# MultiChannelLdc3.net
KiCad netlist of a schematic drawn in Altium Designer
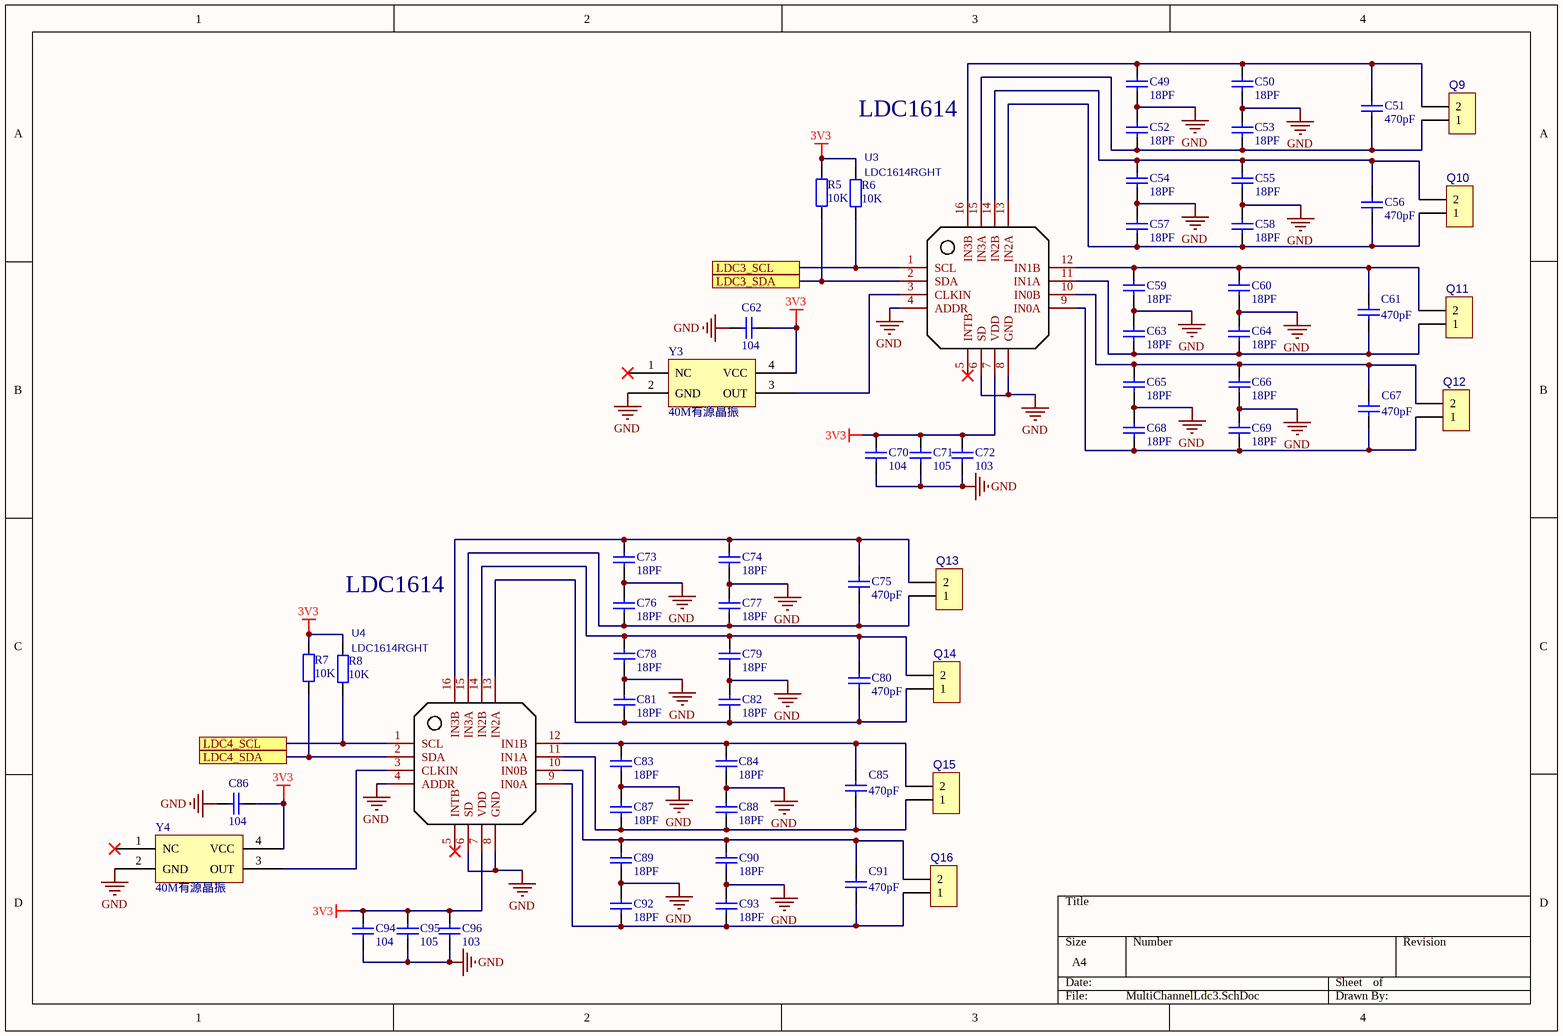
[diagram p0: MultiChannelLdc3.SchDoc]

(export (version "E")
  (design (tool "Eeschema 10.0.6"))
  (components
    (comp (ref "C49")
      (value "18PF")
      (footprint "C0603_L")
      (description "Capacitor")
      (fields (field (name "PUBLISHER") "Altium Limited"))
      (libsource (lib "STM32F103C8T6") (part "Cap"))
    )
    (comp (ref "C50")
      (value "18PF")
      (footprint "C0603_L")
      (description "Capacitor")
      (fields (field (name "PUBLISHER") "Altium Limited"))
      (libsource (lib "STM32F103C8T6") (part "Cap"))
    )
    (comp (ref "C51")
      (value "470pF")
      (footprint "C0603_L")
      (description "Capacitor")
      (fields (field (name "PUBLISHER") "Altium Limited"))
      (libsource (lib "STM32F103C8T6") (part "Cap"))
    )
    (comp (ref "C52")
      (value "18PF")
      (footprint "C0603_L")
      (description "Capacitor")
      (fields (field (name "PUBLISHER") "Altium Limited"))
      (libsource (lib "STM32F103C8T6") (part "Cap"))
    )
    (comp (ref "C53")
      (value "18PF")
      (footprint "C0603_L")
      (description "Capacitor")
      (fields (field (name "PUBLISHER") "Altium Limited"))
      (libsource (lib "STM32F103C8T6") (part "Cap"))
    )
    (comp (ref "C54")
      (value "18PF")
      (footprint "C0603_L")
      (description "Capacitor")
      (fields (field (name "PUBLISHER") "Altium Limited"))
      (libsource (lib "STM32F103C8T6") (part "Cap"))
    )
    (comp (ref "C55")
      (value "18PF")
      (footprint "C0603_L")
      (description "Capacitor")
      (fields (field (name "PUBLISHER") "Altium Limited"))
      (libsource (lib "STM32F103C8T6") (part "Cap"))
    )
    (comp (ref "C56")
      (value "470pF")
      (footprint "C0603_L")
      (description "Capacitor")
      (fields (field (name "PUBLISHER") "Altium Limited"))
      (libsource (lib "STM32F103C8T6") (part "Cap"))
    )
    (comp (ref "C57")
      (value "18PF")
      (footprint "C0603_L")
      (description "Capacitor")
      (fields (field (name "PUBLISHER") "Altium Limited"))
      (libsource (lib "STM32F103C8T6") (part "Cap"))
    )
    (comp (ref "C58")
      (value "18PF")
      (footprint "C0603_L")
      (description "Capacitor")
      (fields (field (name "PUBLISHER") "Altium Limited"))
      (libsource (lib "STM32F103C8T6") (part "Cap"))
    )
    (comp (ref "C59")
      (value "18PF")
      (footprint "C0603_L")
      (description "Capacitor")
      (fields (field (name "PUBLISHER") "Altium Limited"))
      (libsource (lib "STM32F103C8T6") (part "Cap"))
    )
    (comp (ref "C60")
      (value "18PF")
      (footprint "C0603_L")
      (description "Capacitor")
      (fields (field (name "PUBLISHER") "Altium Limited"))
      (libsource (lib "STM32F103C8T6") (part "Cap"))
    )
    (comp (ref "C61")
      (value "470pF")
      (footprint "C0603_L")
      (description "Capacitor")
      (fields (field (name "PUBLISHER") "Altium Limited"))
      (libsource (lib "STM32F103C8T6") (part "Cap"))
    )
    (comp (ref "C62")
      (value "104")
      (footprint "C0603_L")
      (description "贴片电容/MLCC电容")
      (libsource (lib "Ldc1614_Pro") (part "C"))
    )
    (comp (ref "C63")
      (value "18PF")
      (footprint "C0603_L")
      (description "Capacitor")
      (fields (field (name "PUBLISHER") "Altium Limited"))
      (libsource (lib "STM32F103C8T6") (part "Cap"))
    )
    (comp (ref "C64")
      (value "18PF")
      (footprint "C0603_L")
      (description "Capacitor")
      (fields (field (name "PUBLISHER") "Altium Limited"))
      (libsource (lib "STM32F103C8T6") (part "Cap"))
    )
    (comp (ref "C65")
      (value "18PF")
      (footprint "C0603_L")
      (description "Capacitor")
      (fields (field (name "PUBLISHER") "Altium Limited"))
      (libsource (lib "STM32F103C8T6") (part "Cap"))
    )
    (comp (ref "C66")
      (value "18PF")
      (footprint "C0603_L")
      (description "Capacitor")
      (fields (field (name "PUBLISHER") "Altium Limited"))
      (libsource (lib "STM32F103C8T6") (part "Cap"))
    )
    (comp (ref "C67")
      (value "470pF")
      (footprint "C0603_L")
      (description "Capacitor")
      (fields (field (name "PUBLISHER") "Altium Limited"))
      (libsource (lib "STM32F103C8T6") (part "Cap"))
    )
    (comp (ref "C68")
      (value "18PF")
      (footprint "C0603_L")
      (description "Capacitor")
      (fields (field (name "PUBLISHER") "Altium Limited"))
      (libsource (lib "STM32F103C8T6") (part "Cap"))
    )
    (comp (ref "C69")
      (value "18PF")
      (footprint "C0603_L")
      (description "Capacitor")
      (fields (field (name "PUBLISHER") "Altium Limited"))
      (libsource (lib "STM32F103C8T6") (part "Cap"))
    )
    (comp (ref "C70")
      (value "104")
      (footprint "C0603_L")
      (description "Capacitor")
      (fields (field (name "PUBLISHER") "Altium Limited"))
      (libsource (lib "STM32F103C8T6") (part "Cap"))
    )
    (comp (ref "C71")
      (value "105")
      (footprint "C0603_L")
      (description "Capacitor")
      (fields (field (name "PUBLISHER") "Altium Limited"))
      (libsource (lib "STM32F103C8T6") (part "Cap"))
    )
    (comp (ref "C72")
      (value "103")
      (footprint "C0603_L")
      (description "Capacitor")
      (fields (field (name "PUBLISHER") "Altium Limited"))
      (libsource (lib "STM32F103C8T6") (part "Cap"))
    )
    (comp (ref "C73")
      (value "18PF")
      (footprint "C0603_L")
      (description "Capacitor")
      (fields (field (name "PUBLISHER") "Altium Limited"))
      (libsource (lib "STM32F103C8T6") (part "Cap"))
    )
    (comp (ref "C74")
      (value "18PF")
      (footprint "C0603_L")
      (description "Capacitor")
      (fields (field (name "PUBLISHER") "Altium Limited"))
      (libsource (lib "STM32F103C8T6") (part "Cap"))
    )
    (comp (ref "C75")
      (value "470pF")
      (footprint "C0603_L")
      (description "Capacitor")
      (fields (field (name "PUBLISHER") "Altium Limited"))
      (libsource (lib "STM32F103C8T6") (part "Cap"))
    )
    (comp (ref "C76")
      (value "18PF")
      (footprint "C0603_L")
      (description "Capacitor")
      (fields (field (name "PUBLISHER") "Altium Limited"))
      (libsource (lib "STM32F103C8T6") (part "Cap"))
    )
    (comp (ref "C77")
      (value "18PF")
      (footprint "C0603_L")
      (description "Capacitor")
      (fields (field (name "PUBLISHER") "Altium Limited"))
      (libsource (lib "STM32F103C8T6") (part "Cap"))
    )
    (comp (ref "C78")
      (value "18PF")
      (footprint "C0603_L")
      (description "Capacitor")
      (fields (field (name "PUBLISHER") "Altium Limited"))
      (libsource (lib "STM32F103C8T6") (part "Cap"))
    )
    (comp (ref "C79")
      (value "18PF")
      (footprint "C0603_L")
      (description "Capacitor")
      (fields (field (name "PUBLISHER") "Altium Limited"))
      (libsource (lib "STM32F103C8T6") (part "Cap"))
    )
    (comp (ref "C80")
      (value "470pF")
      (footprint "C0603_L")
      (description "Capacitor")
      (fields (field (name "PUBLISHER") "Altium Limited"))
      (libsource (lib "STM32F103C8T6") (part "Cap"))
    )
    (comp (ref "C81")
      (value "18PF")
      (footprint "C0603_L")
      (description "Capacitor")
      (fields (field (name "PUBLISHER") "Altium Limited"))
      (libsource (lib "STM32F103C8T6") (part "Cap"))
    )
    (comp (ref "C82")
      (value "18PF")
      (footprint "C0603_L")
      (description "Capacitor")
      (fields (field (name "PUBLISHER") "Altium Limited"))
      (libsource (lib "STM32F103C8T6") (part "Cap"))
    )
    (comp (ref "C83")
      (value "18PF")
      (footprint "C0603_L")
      (description "Capacitor")
      (fields (field (name "PUBLISHER") "Altium Limited"))
      (libsource (lib "STM32F103C8T6") (part "Cap"))
    )
    (comp (ref "C84")
      (value "18PF")
      (footprint "C0603_L")
      (description "Capacitor")
      (fields (field (name "PUBLISHER") "Altium Limited"))
      (libsource (lib "STM32F103C8T6") (part "Cap"))
    )
    (comp (ref "C85")
      (value "470pF")
      (footprint "C0603_L")
      (description "Capacitor")
      (fields (field (name "PUBLISHER") "Altium Limited"))
      (libsource (lib "STM32F103C8T6") (part "Cap"))
    )
    (comp (ref "C86")
      (value "104")
      (footprint "C0603_L")
      (description "贴片电容/MLCC电容")
      (libsource (lib "Ldc1614_Pro") (part "C"))
    )
    (comp (ref "C87")
      (value "18PF")
      (footprint "C0603_L")
      (description "Capacitor")
      (fields (field (name "PUBLISHER") "Altium Limited"))
      (libsource (lib "STM32F103C8T6") (part "Cap"))
    )
    (comp (ref "C88")
      (value "18PF")
      (footprint "C0603_L")
      (description "Capacitor")
      (fields (field (name "PUBLISHER") "Altium Limited"))
      (libsource (lib "STM32F103C8T6") (part "Cap"))
    )
    (comp (ref "C89")
      (value "18PF")
      (footprint "C0603_L")
      (description "Capacitor")
      (fields (field (name "PUBLISHER") "Altium Limited"))
      (libsource (lib "STM32F103C8T6") (part "Cap"))
    )
    (comp (ref "C90")
      (value "18PF")
      (footprint "C0603_L")
      (description "Capacitor")
      (fields (field (name "PUBLISHER") "Altium Limited"))
      (libsource (lib "STM32F103C8T6") (part "Cap"))
    )
    (comp (ref "C91")
      (value "470pF")
      (footprint "C0603_L")
      (description "Capacitor")
      (fields (field (name "PUBLISHER") "Altium Limited"))
      (libsource (lib "STM32F103C8T6") (part "Cap"))
    )
    (comp (ref "C92")
      (value "18PF")
      (footprint "C0603_L")
      (description "Capacitor")
      (fields (field (name "PUBLISHER") "Altium Limited"))
      (libsource (lib "STM32F103C8T6") (part "Cap"))
    )
    (comp (ref "C93")
      (value "18PF")
      (footprint "C0603_L")
      (description "Capacitor")
      (fields (field (name "PUBLISHER") "Altium Limited"))
      (libsource (lib "STM32F103C8T6") (part "Cap"))
    )
    (comp (ref "C94")
      (value "104")
      (footprint "C0603_L")
      (description "Capacitor")
      (fields (field (name "PUBLISHER") "Altium Limited"))
      (libsource (lib "STM32F103C8T6") (part "Cap"))
    )
    (comp (ref "C95")
      (value "105")
      (footprint "C0603_L")
      (description "Capacitor")
      (fields (field (name "PUBLISHER") "Altium Limited"))
      (libsource (lib "STM32F103C8T6") (part "Cap"))
    )
    (comp (ref "C96")
      (value "103")
      (footprint "C0603_L")
      (description "Capacitor")
      (fields (field (name "PUBLISHER") "Altium Limited"))
      (libsource (lib "STM32F103C8T6") (part "Cap"))
    )
    (comp (ref "Q9")
      (value "~")
      (footprint "座子")
      (description "Connector")
      (libsource (lib "*") (part "CON2"))
    )
    (comp (ref "Q10")
      (value "~")
      (footprint "座子")
      (description "Connector")
      (libsource (lib "*") (part "CON2"))
    )
    (comp (ref "Q11")
      (value "~")
      (footprint "座子")
      (description "Connector")
      (libsource (lib "*") (part "CON2"))
    )
    (comp (ref "Q12")
      (value "~")
      (footprint "座子")
      (description "Connector")
      (libsource (lib "*") (part "CON2"))
    )
    (comp (ref "Q13")
      (value "~")
      (footprint "座子")
      (description "Connector")
      (libsource (lib "*") (part "CON2"))
    )
    (comp (ref "Q14")
      (value "~")
      (footprint "座子")
      (description "Connector")
      (libsource (lib "*") (part "CON2"))
    )
    (comp (ref "Q15")
      (value "~")
      (footprint "座子")
      (description "Connector")
      (libsource (lib "*") (part "CON2"))
    )
    (comp (ref "Q16")
      (value "~")
      (footprint "座子")
      (description "Connector")
      (libsource (lib "*") (part "CON2"))
    )
    (comp (ref "R5")
      (value "10K")
      (footprint "R0603_L")
      (description "Resistor")
      (fields (field (name "Comment") "Res2") (field (name "PUBLISHER") "Altium Limited"))
      (libsource (lib "LDC") (part "Res2"))
    )
    (comp (ref "R6")
      (value "10K")
      (footprint "R0603_L")
      (description "Resistor")
      (fields (field (name "Comment") "Res2") (field (name "PUBLISHER") "Altium Limited"))
      (libsource (lib "Miscellaneous Devices") (part "Res2"))
    )
    (comp (ref "R7")
      (value "10K")
      (footprint "R0603_L")
      (description "Resistor")
      (fields (field (name "Comment") "Res2") (field (name "PUBLISHER") "Altium Limited"))
      (libsource (lib "LDC") (part "Res2"))
    )
    (comp (ref "R8")
      (value "10K")
      (footprint "R0603_L")
      (description "Resistor")
      (fields (field (name "Comment") "Res2") (field (name "PUBLISHER") "Altium Limited"))
      (libsource (lib "Miscellaneous Devices") (part "Res2"))
    )
    (comp (ref "U3")
      (value "LDC1614RGHT")
      (footprint "W-QFN-16")
      (fields
        (field (name "BOM_MANUFACTURER PART") "LDC1314RGHT")
        (field (name "BOM_SUPPLIER PART") "C80399")
      )
      (libsource (lib "LDC1614") (part "LDC1614RGHT"))
    )
    (comp (ref "U4")
      (value "LDC1614RGHT")
      (footprint "W-QFN-16")
      (fields
        (field (name "BOM_MANUFACTURER PART") "LDC1314RGHT")
        (field (name "BOM_SUPPLIER PART") "C80399")
      )
      (libsource (lib "LDC1614") (part "LDC1614RGHT"))
    )
    (comp (ref "Y3") (value "40M有源晶振") (footprint "SMD3225") (libsource (lib "其他常用元件类") (part "有源晶振")))
    (comp (ref "Y4") (value "40M有源晶振") (footprint "SMD3225") (libsource (lib "其他常用元件类") (part "有源晶振")))
  )
  (nets
    (net (code "1") (name "/LDC3_SCL") (class "Default")
      (node (ref "U3") (pin "1") (pinfunction "SCL_1") (pintype "passive"))
    )
    (net (code "2") (name "/LDC3_SDA") (class "Default")
      (node (ref "R5") (pin "1") (pinfunction "1_1") (pintype "passive"))
      (node (ref "U3") (pin "2") (pinfunction "SDA_2") (pintype "passive"))
    )
    (net (code "3") (name "/LDC4_SCL") (class "Default")
      (node (ref "U4") (pin "1") (pinfunction "SCL_1") (pintype "passive"))
    )
    (net (code "4") (name "/LDC4_SDA") (class "Default")
      (node (ref "R7") (pin "1") (pinfunction "1_1") (pintype "passive"))
      (node (ref "U4") (pin "2") (pinfunction "SDA_2") (pintype "passive"))
    )
    (net (code "5") (name "3V3") (class "Default")
      (node (ref "C62") (pin "1") (pinfunction "1_1") (pintype "passive"))
      (node (ref "C70") (pin "1") (pinfunction "1_1") (pintype "passive"))
      (node (ref "C71") (pin "1") (pinfunction "1_1") (pintype "passive"))
      (node (ref "C72") (pin "1") (pinfunction "1_1") (pintype "passive"))
      (node (ref "C86") (pin "1") (pinfunction "1_1") (pintype "passive"))
      (node (ref "C94") (pin "1") (pinfunction "1_1") (pintype "passive"))
      (node (ref "C95") (pin "1") (pinfunction "1_1") (pintype "passive"))
      (node (ref "C96") (pin "1") (pinfunction "1_1") (pintype "passive"))
      (node (ref "R5") (pin "2") (pinfunction "2_2") (pintype "passive"))
      (node (ref "R6") (pin "1") (pinfunction "1_1") (pintype "passive"))
      (node (ref "R7") (pin "2") (pinfunction "2_2") (pintype "passive"))
      (node (ref "R8") (pin "1") (pinfunction "1_1") (pintype "passive"))
      (node (ref "U3") (pin "7") (pinfunction "VDD_7") (pintype "passive"))
      (node (ref "U4") (pin "7") (pinfunction "VDD_7") (pintype "passive"))
      (node (ref "Y3") (pin "4") (pinfunction "VCC_4") (pintype "passive"))
      (node (ref "Y4") (pin "4") (pinfunction "VCC_4") (pintype "passive"))
    )
    (net (code "6") (name "GND") (class "Default")
      (node (ref "C49") (pin "2") (pinfunction "2_2") (pintype "passive"))
      (node (ref "C50") (pin "2") (pinfunction "2_2") (pintype "passive"))
      (node (ref "C52") (pin "1") (pinfunction "1_1") (pintype "passive"))
      (node (ref "C53") (pin "1") (pinfunction "1_1") (pintype "passive"))
      (node (ref "C54") (pin "2") (pinfunction "2_2") (pintype "passive"))
      (node (ref "C55") (pin "2") (pinfunction "2_2") (pintype "passive"))
      (node (ref "C57") (pin "1") (pinfunction "1_1") (pintype "passive"))
      (node (ref "C58") (pin "1") (pinfunction "1_1") (pintype "passive"))
      (node (ref "C59") (pin "2") (pinfunction "2_2") (pintype "passive"))
      (node (ref "C60") (pin "2") (pinfunction "2_2") (pintype "passive"))
      (node (ref "C62") (pin "2") (pinfunction "2_2") (pintype "passive"))
      (node (ref "C63") (pin "1") (pinfunction "1_1") (pintype "passive"))
      (node (ref "C64") (pin "1") (pinfunction "1_1") (pintype "passive"))
      (node (ref "C65") (pin "2") (pinfunction "2_2") (pintype "passive"))
      (node (ref "C66") (pin "2") (pinfunction "2_2") (pintype "passive"))
      (node (ref "C68") (pin "1") (pinfunction "1_1") (pintype "passive"))
      (node (ref "C69") (pin "1") (pinfunction "1_1") (pintype "passive"))
      (node (ref "C70") (pin "2") (pinfunction "2_2") (pintype "passive"))
      (node (ref "C71") (pin "2") (pinfunction "2_2") (pintype "passive"))
      (node (ref "C72") (pin "2") (pinfunction "2_2") (pintype "passive"))
      (node (ref "C73") (pin "2") (pinfunction "2_2") (pintype "passive"))
      (node (ref "C74") (pin "2") (pinfunction "2_2") (pintype "passive"))
      (node (ref "C76") (pin "1") (pinfunction "1_1") (pintype "passive"))
      (node (ref "C77") (pin "1") (pinfunction "1_1") (pintype "passive"))
      (node (ref "C78") (pin "2") (pinfunction "2_2") (pintype "passive"))
      (node (ref "C79") (pin "2") (pinfunction "2_2") (pintype "passive"))
      (node (ref "C81") (pin "1") (pinfunction "1_1") (pintype "passive"))
      (node (ref "C82") (pin "1") (pinfunction "1_1") (pintype "passive"))
      (node (ref "C83") (pin "2") (pinfunction "2_2") (pintype "passive"))
      (node (ref "C84") (pin "2") (pinfunction "2_2") (pintype "passive"))
      (node (ref "C86") (pin "2") (pinfunction "2_2") (pintype "passive"))
      (node (ref "C87") (pin "1") (pinfunction "1_1") (pintype "passive"))
      (node (ref "C88") (pin "1") (pinfunction "1_1") (pintype "passive"))
      (node (ref "C89") (pin "2") (pinfunction "2_2") (pintype "passive"))
      (node (ref "C90") (pin "2") (pinfunction "2_2") (pintype "passive"))
      (node (ref "C92") (pin "1") (pinfunction "1_1") (pintype "passive"))
      (node (ref "C93") (pin "1") (pinfunction "1_1") (pintype "passive"))
      (node (ref "C94") (pin "2") (pinfunction "2_2") (pintype "passive"))
      (node (ref "C95") (pin "2") (pinfunction "2_2") (pintype "passive"))
      (node (ref "C96") (pin "2") (pinfunction "2_2") (pintype "passive"))
      (node (ref "U3") (pin "4") (pinfunction "ADDR_4") (pintype "passive"))
      (node (ref "U3") (pin "6") (pinfunction "SD_6") (pintype "passive"))
      (node (ref "U3") (pin "8") (pinfunction "GND_8") (pintype "passive"))
      (node (ref "U4") (pin "4") (pinfunction "ADDR_4") (pintype "passive"))
      (node (ref "U4") (pin "6") (pinfunction "SD_6") (pintype "passive"))
      (node (ref "U4") (pin "8") (pinfunction "GND_8") (pintype "passive"))
      (node (ref "Y3") (pin "2") (pinfunction "GND_2") (pintype "passive"))
      (node (ref "Y4") (pin "2") (pinfunction "GND_2") (pintype "passive"))
    )
    (net (code "7") (name "Net-(U3-CLKIN)") (class "Default")
      (node (ref "U3") (pin "3") (pinfunction "CLKIN_3") (pintype "passive"))
      (node (ref "Y3") (pin "3") (pinfunction "OUT_3") (pintype "passive"))
    )
    (net (code "8") (name "Net-(U3-IN0A)") (class "Default")
      (node (ref "C67") (pin "1") (pinfunction "1_1") (pintype "passive"))
      (node (ref "C68") (pin "2") (pinfunction "2_2") (pintype "passive"))
      (node (ref "C69") (pin "2") (pinfunction "2_2") (pintype "passive"))
      (node (ref "Q12") (pin "1") (pinfunction "1_1") (pintype "passive"))
      (node (ref "U3") (pin "9") (pinfunction "IN0A_9") (pintype "passive"))
    )
    (net (code "9") (name "Net-(U3-IN0B)") (class "Default")
      (node (ref "C65") (pin "1") (pinfunction "1_1") (pintype "passive"))
      (node (ref "C66") (pin "1") (pinfunction "1_1") (pintype "passive"))
      (node (ref "C67") (pin "2") (pinfunction "2_2") (pintype "passive"))
      (node (ref "Q12") (pin "2") (pinfunction "2_2") (pintype "passive"))
      (node (ref "U3") (pin "10") (pinfunction "IN0B_10") (pintype "passive"))
    )
    (net (code "10") (name "Net-(U3-IN1A)") (class "Default")
      (node (ref "C61") (pin "1") (pinfunction "1_1") (pintype "passive"))
      (node (ref "C63") (pin "2") (pinfunction "2_2") (pintype "passive"))
      (node (ref "C64") (pin "2") (pinfunction "2_2") (pintype "passive"))
      (node (ref "Q11") (pin "1") (pinfunction "1_1") (pintype "passive"))
      (node (ref "U3") (pin "11") (pinfunction "IN1A_11") (pintype "passive"))
    )
    (net (code "11") (name "Net-(U3-IN1B)") (class "Default")
      (node (ref "C59") (pin "1") (pinfunction "1_1") (pintype "passive"))
      (node (ref "C60") (pin "1") (pinfunction "1_1") (pintype "passive"))
      (node (ref "C61") (pin "2") (pinfunction "2_2") (pintype "passive"))
      (node (ref "Q11") (pin "2") (pinfunction "2_2") (pintype "passive"))
      (node (ref "U3") (pin "12") (pinfunction "IN1B_12") (pintype "passive"))
    )
    (net (code "12") (name "Net-(U3-IN2A)") (class "Default")
      (node (ref "C56") (pin "1") (pinfunction "1_1") (pintype "passive"))
      (node (ref "C57") (pin "2") (pinfunction "2_2") (pintype "passive"))
      (node (ref "C58") (pin "2") (pinfunction "2_2") (pintype "passive"))
      (node (ref "Q10") (pin "1") (pinfunction "1_1") (pintype "passive"))
      (node (ref "U3") (pin "13") (pinfunction "IN2A_13") (pintype "passive"))
    )
    (net (code "13") (name "Net-(U3-IN2B)") (class "Default")
      (node (ref "C54") (pin "1") (pinfunction "1_1") (pintype "passive"))
      (node (ref "C55") (pin "1") (pinfunction "1_1") (pintype "passive"))
      (node (ref "C56") (pin "2") (pinfunction "2_2") (pintype "passive"))
      (node (ref "Q10") (pin "2") (pinfunction "2_2") (pintype "passive"))
      (node (ref "U3") (pin "14") (pinfunction "IN2B_14") (pintype "passive"))
    )
    (net (code "14") (name "Net-(U3-IN3A)") (class "Default")
      (node (ref "C51") (pin "1") (pinfunction "1_1") (pintype "passive"))
      (node (ref "C52") (pin "2") (pinfunction "2_2") (pintype "passive"))
      (node (ref "C53") (pin "2") (pinfunction "2_2") (pintype "passive"))
      (node (ref "Q9") (pin "1") (pinfunction "1_1") (pintype "passive"))
      (node (ref "U3") (pin "15") (pinfunction "IN3A_15") (pintype "passive"))
    )
    (net (code "15") (name "Net-(U3-IN3B)") (class "Default")
      (node (ref "C49") (pin "1") (pinfunction "1_1") (pintype "passive"))
      (node (ref "C50") (pin "1") (pinfunction "1_1") (pintype "passive"))
      (node (ref "C51") (pin "2") (pinfunction "2_2") (pintype "passive"))
      (node (ref "Q9") (pin "2") (pinfunction "2_2") (pintype "passive"))
      (node (ref "U3") (pin "16") (pinfunction "IN3B_16") (pintype "passive"))
    )
    (net (code "16") (name "Net-(U4-CLKIN)") (class "Default")
      (node (ref "U4") (pin "3") (pinfunction "CLKIN_3") (pintype "passive"))
      (node (ref "Y4") (pin "3") (pinfunction "OUT_3") (pintype "passive"))
    )
    (net (code "17") (name "Net-(U4-IN0A)") (class "Default")
      (node (ref "C91") (pin "1") (pinfunction "1_1") (pintype "passive"))
      (node (ref "C92") (pin "2") (pinfunction "2_2") (pintype "passive"))
      (node (ref "C93") (pin "2") (pinfunction "2_2") (pintype "passive"))
      (node (ref "Q16") (pin "1") (pinfunction "1_1") (pintype "passive"))
      (node (ref "U4") (pin "9") (pinfunction "IN0A_9") (pintype "passive"))
    )
    (net (code "18") (name "Net-(U4-IN0B)") (class "Default")
      (node (ref "C89") (pin "1") (pinfunction "1_1") (pintype "passive"))
      (node (ref "C90") (pin "1") (pinfunction "1_1") (pintype "passive"))
      (node (ref "C91") (pin "2") (pinfunction "2_2") (pintype "passive"))
      (node (ref "Q16") (pin "2") (pinfunction "2_2") (pintype "passive"))
      (node (ref "U4") (pin "10") (pinfunction "IN0B_10") (pintype "passive"))
    )
    (net (code "19") (name "Net-(U4-IN1A)") (class "Default")
      (node (ref "C85") (pin "1") (pinfunction "1_1") (pintype "passive"))
      (node (ref "C87") (pin "2") (pinfunction "2_2") (pintype "passive"))
      (node (ref "C88") (pin "2") (pinfunction "2_2") (pintype "passive"))
      (node (ref "Q15") (pin "1") (pinfunction "1_1") (pintype "passive"))
      (node (ref "U4") (pin "11") (pinfunction "IN1A_11") (pintype "passive"))
    )
    (net (code "20") (name "Net-(U4-IN1B)") (class "Default")
      (node (ref "C83") (pin "1") (pinfunction "1_1") (pintype "passive"))
      (node (ref "C84") (pin "1") (pinfunction "1_1") (pintype "passive"))
      (node (ref "C85") (pin "2") (pinfunction "2_2") (pintype "passive"))
      (node (ref "Q15") (pin "2") (pinfunction "2_2") (pintype "passive"))
      (node (ref "U4") (pin "12") (pinfunction "IN1B_12") (pintype "passive"))
    )
    (net (code "21") (name "Net-(U4-IN2A)") (class "Default")
      (node (ref "C80") (pin "1") (pinfunction "1_1") (pintype "passive"))
      (node (ref "C81") (pin "2") (pinfunction "2_2") (pintype "passive"))
      (node (ref "C82") (pin "2") (pinfunction "2_2") (pintype "passive"))
      (node (ref "Q14") (pin "1") (pinfunction "1_1") (pintype "passive"))
      (node (ref "U4") (pin "13") (pinfunction "IN2A_13") (pintype "passive"))
    )
    (net (code "22") (name "Net-(U4-IN2B)") (class "Default")
      (node (ref "C78") (pin "1") (pinfunction "1_1") (pintype "passive"))
      (node (ref "C79") (pin "1") (pinfunction "1_1") (pintype "passive"))
      (node (ref "C80") (pin "2") (pinfunction "2_2") (pintype "passive"))
      (node (ref "Q14") (pin "2") (pinfunction "2_2") (pintype "passive"))
      (node (ref "U4") (pin "14") (pinfunction "IN2B_14") (pintype "passive"))
    )
    (net (code "23") (name "Net-(U4-IN3A)") (class "Default")
      (node (ref "C75") (pin "1") (pinfunction "1_1") (pintype "passive"))
      (node (ref "C76") (pin "2") (pinfunction "2_2") (pintype "passive"))
      (node (ref "C77") (pin "2") (pinfunction "2_2") (pintype "passive"))
      (node (ref "Q13") (pin "1") (pinfunction "1_1") (pintype "passive"))
      (node (ref "U4") (pin "15") (pinfunction "IN3A_15") (pintype "passive"))
    )
    (net (code "24") (name "Net-(U4-IN3B)") (class "Default")
      (node (ref "C73") (pin "1") (pinfunction "1_1") (pintype "passive"))
      (node (ref "C74") (pin "1") (pinfunction "1_1") (pintype "passive"))
      (node (ref "C75") (pin "2") (pinfunction "2_2") (pintype "passive"))
      (node (ref "Q13") (pin "2") (pinfunction "2_2") (pintype "passive"))
      (node (ref "U4") (pin "16") (pinfunction "IN3B_16") (pintype "passive"))
    )
    (net (code "25") (name "unconnected-(R6-Pad2)") (class "Default")
      (node (ref "R6") (pin "2") (pinfunction "2_2") (pintype "passive"))
    )
    (net (code "26") (name "unconnected-(R8-Pad2)") (class "Default")
      (node (ref "R8") (pin "2") (pinfunction "2_2") (pintype "passive"))
    )
    (net (code "27") (name "unconnected-(U3-INTB-Pad5)") (class "Default")
      (node (ref "U3") (pin "5") (pinfunction "INTB_5") (pintype "passive+no_connect"))
    )
    (net (code "28") (name "unconnected-(U4-INTB-Pad5)") (class "Default")
      (node (ref "U4") (pin "5") (pinfunction "INTB_5") (pintype "passive+no_connect"))
    )
    (net (code "29") (name "unconnected-(Y3-NC-Pad1)") (class "Default")
      (node (ref "Y3") (pin "1") (pinfunction "NC_1") (pintype "passive+no_connect"))
    )
    (net (code "30") (name "unconnected-(Y4-NC-Pad1)") (class "Default")
      (node (ref "Y4") (pin "1") (pinfunction "NC_1") (pintype "passive+no_connect"))
    )
  )
)
